# mh.net
KiCad netlist of a schematic drawn in EAGLE
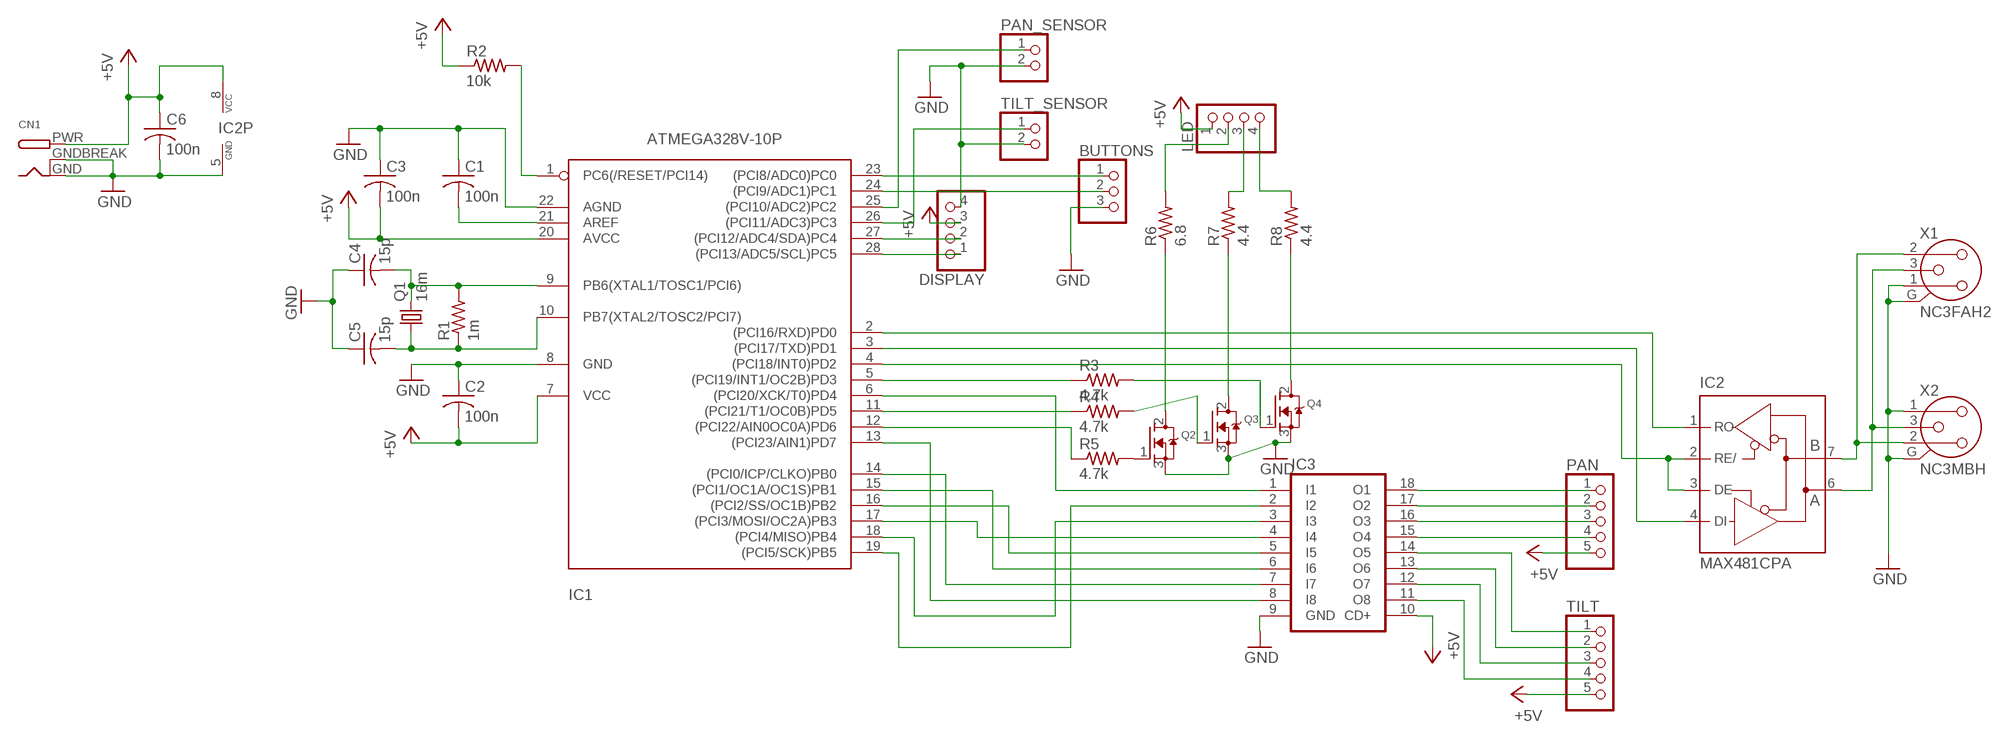
[diagram p0: schematic, sheet 1]

(export (version "E")
  (design (tool "Eeschema 10.0.6"))
  (components
    (comp (ref "BUTTONS")
      (value "PINHD-1X3")
      (footprint "eagle-import:1X03")
      (libsource (lib "eagle-import") (part "PINHD-1X3"))
    )
    (comp (ref "C1")
      (value "100n")
      (footprint "eagle-import:C025-024X044")
      (libsource (lib "eagle-import") (part "C-US025-024X044"))
    )
    (comp (ref "C2")
      (value "100n")
      (footprint "eagle-import:C025-024X044")
      (libsource (lib "eagle-import") (part "C-US025-024X044"))
    )
    (comp (ref "C3")
      (value "100n")
      (footprint "eagle-import:C025-024X044")
      (libsource (lib "eagle-import") (part "C-US025-024X044"))
    )
    (comp (ref "C4")
      (value "15p")
      (footprint "eagle-import:C050-024X044")
      (libsource (lib "eagle-import") (part "C-US050-024X044"))
    )
    (comp (ref "C5")
      (value "15p")
      (footprint "eagle-import:C050-024X044")
      (libsource (lib "eagle-import") (part "C-US050-024X044"))
    )
    (comp (ref "C6")
      (value "100n")
      (footprint "eagle-import:C025-024X044")
      (libsource (lib "eagle-import") (part "C-US025-024X044"))
    )
    (comp (ref "CN1")
      (value "DCBARRELPTH")
      (footprint "eagle-import:DCJACK_2MM_PTH")
      (libsource (lib "eagle-import") (part "DCBARRELPTH"))
    )
    (comp (ref "DISPLAY")
      (value "PINHD-1X4")
      (footprint "eagle-import:1X04")
      (libsource (lib "eagle-import") (part "PINHD-1X4"))
    )
    (comp (ref "IC1")
      (value "ATMEGA328V-10P")
      (footprint "eagle-import:DIL28-3")
      (libsource (lib "eagle-import") (part "ATMEGA328PV-10"))
    )
    (comp (ref "IC2")
      (value "MAX481CPA")
      (footprint "eagle-import:DIL08")
      (fields (field (name "MPN") "MAX481CPA+"))
      (libsource (lib "eagle-import") (part "MAX481CPA"))
    )
    (comp (ref "IC3")
      (value "ULN2803A")
      (footprint "eagle-import:DIL18")
      (libsource (lib "eagle-import") (part "ULN2803A"))
    )
    (comp (ref "LED")
      (value "PINHD-1X4")
      (footprint "eagle-import:1X04")
      (libsource (lib "eagle-import") (part "PINHD-1X4"))
    )
    (comp (ref "PAN")
      (value "PINHD-1X5")
      (footprint "eagle-import:1X05")
      (libsource (lib "eagle-import") (part "PINHD-1X5"))
    )
    (comp (ref "PAN_SENSOR")
      (value "PINHD-1X2")
      (footprint "eagle-import:1X02")
      (libsource (lib "eagle-import") (part "PINHD-1X2"))
    )
    (comp (ref "Q1")
      (value "16m")
      (footprint "eagle-import:HC49_S")
      (libsource (lib "eagle-import") (part "CRYSTALHC49S"))
    )
    (comp (ref "Q2")
      (value "MOSFET-NGDS_TO220V")
      (footprint "eagle-import:TO220V")
      (libsource (lib "eagle-import") (part "MOSFET-NGDS_TO220V"))
    )
    (comp (ref "Q3")
      (value "MOSFET-NGDS_TO220V")
      (footprint "eagle-import:TO220V")
      (libsource (lib "eagle-import") (part "MOSFET-NGDS_TO220V"))
    )
    (comp (ref "Q4")
      (value "MOSFET-NGDS_TO220V")
      (footprint "eagle-import:TO220V")
      (libsource (lib "eagle-import") (part "MOSFET-NGDS_TO220V"))
    )
    (comp (ref "R1")
      (value "1m")
      (footprint "eagle-import:0207_10")
      (libsource (lib "eagle-import") (part "R-US_0207/10"))
    )
    (comp (ref "R2")
      (value "10k")
      (footprint "eagle-import:0207_10")
      (libsource (lib "eagle-import") (part "R-US_0207/10"))
    )
    (comp (ref "R3")
      (value "4.7k")
      (footprint "eagle-import:0207_10")
      (libsource (lib "eagle-import") (part "R-US_0207/10"))
    )
    (comp (ref "R4")
      (value "4.7k")
      (footprint "eagle-import:0207_10")
      (libsource (lib "eagle-import") (part "R-US_0207/10"))
    )
    (comp (ref "R5")
      (value "4.7k")
      (footprint "eagle-import:0207_10")
      (libsource (lib "eagle-import") (part "R-US_0207/10"))
    )
    (comp (ref "R6")
      (value "6.8")
      (footprint "eagle-import:0617_17")
      (libsource (lib "eagle-import") (part "R-US_0617/17"))
    )
    (comp (ref "R7")
      (value "4.4")
      (footprint "eagle-import:0617_17")
      (libsource (lib "eagle-import") (part "R-US_0617/17"))
    )
    (comp (ref "R8")
      (value "4.4")
      (footprint "eagle-import:0617_17")
      (libsource (lib "eagle-import") (part "R-US_0617/17"))
    )
    (comp (ref "TILT")
      (value "PINHD-1X5")
      (footprint "eagle-import:1X05")
      (libsource (lib "eagle-import") (part "PINHD-1X5"))
    )
    (comp (ref "TILT_SENSOR")
      (value "PINHD-1X2")
      (footprint "eagle-import:1X02")
      (libsource (lib "eagle-import") (part "PINHD-1X2"))
    )
    (comp (ref "X1")
      (value "NC3FAH2")
      (footprint "eagle-import:NC3FAH2")
      (libsource (lib "eagle-import") (part "NC3FAH2"))
    )
    (comp (ref "X2")
      (value "NC3MBH")
      (footprint "eagle-import:NC3MBH")
      (fields (field (name "MF") "NEUTRIK"))
      (libsource (lib "eagle-import") (part "NC3MBH"))
    )
  )
  (nets
    (net (code "1") (name "+5V") (class "Default")
      (node (ref "C2") (pin "2") (pinfunction "2_2") (pintype "passive"))
      (node (ref "C3") (pin "2") (pinfunction "2_2") (pintype "passive"))
      (node (ref "C6") (pin "1") (pinfunction "1_1") (pintype "passive"))
      (node (ref "CN1") (pin "PWR") (pinfunction "PWR_PWR") (pintype "power_in"))
      (node (ref "DISPLAY") (pin "3") (pinfunction "3_3") (pintype "passive"))
      (node (ref "IC1") (pin "20") (pinfunction "AVCC_20") (pintype "bidirectional"))
      (node (ref "IC1") (pin "7") (pinfunction "VCC_7") (pintype "bidirectional"))
      (node (ref "IC2") (pin "8") (pinfunction "VCC_8") (pintype "power_in"))
      (node (ref "IC3") (pin "10") (pinfunction "CD+_10") (pintype "passive"))
      (node (ref "LED") (pin "1") (pinfunction "1_1") (pintype "passive"))
      (node (ref "PAN") (pin "5") (pinfunction "5_5") (pintype "passive"))
      (node (ref "R2") (pin "1") (pinfunction "1_1") (pintype "passive"))
      (node (ref "TILT") (pin "5") (pinfunction "5_5") (pintype "passive"))
    )
    (net (code "2") (name "GND") (class "Default")
      (node (ref "BUTTONS") (pin "3") (pinfunction "3_3") (pintype "passive"))
      (node (ref "C1") (pin "1") (pinfunction "1_1") (pintype "passive"))
      (node (ref "C2") (pin "1") (pinfunction "1_1") (pintype "passive"))
      (node (ref "C3") (pin "1") (pinfunction "1_1") (pintype "passive"))
      (node (ref "C4") (pin "1") (pinfunction "1_1") (pintype "passive"))
      (node (ref "C5") (pin "1") (pinfunction "1_1") (pintype "passive"))
      (node (ref "C6") (pin "2") (pinfunction "2_2") (pintype "passive"))
      (node (ref "CN1") (pin "GND") (pinfunction "GND_GND") (pintype "power_in"))
      (node (ref "CN1") (pin "GNDBREAK") (pinfunction "GNDBREAK_GNDBREAK") (pintype "power_in"))
      (node (ref "DISPLAY") (pin "4") (pinfunction "4_4") (pintype "passive"))
      (node (ref "IC1") (pin "22") (pinfunction "AGND_22") (pintype "bidirectional"))
      (node (ref "IC1") (pin "8") (pinfunction "GND_8") (pintype "bidirectional"))
      (node (ref "IC2") (pin "5") (pinfunction "GND_5") (pintype "power_in"))
      (node (ref "IC3") (pin "9") (pinfunction "GND_9") (pintype "power_in"))
      (node (ref "PAN_SENSOR") (pin "2") (pinfunction "2_2") (pintype "passive"))
      (node (ref "Q2") (pin "3") (pinfunction "S_3") (pintype "bidirectional"))
      (node (ref "Q3") (pin "3") (pinfunction "S_3") (pintype "bidirectional"))
      (node (ref "Q4") (pin "3") (pinfunction "S_3") (pintype "bidirectional"))
      (node (ref "TILT_SENSOR") (pin "2") (pinfunction "2_2") (pintype "passive"))
      (node (ref "X1") (pin "1") (pinfunction "2_1") (pintype "passive"))
      (node (ref "X1") (pin "G") (pinfunction "G_G") (pintype "passive"))
      (node (ref "X2") (pin "1") (pinfunction "1_1") (pintype "passive"))
      (node (ref "X2") (pin "G") (pinfunction "G_G") (pintype "passive"))
    )
    (net (code "3") (name "Net-(IC1-(PCI0{slash}ICP{slash}CLKO)PB0)") (class "Default")
      (node (ref "IC1") (pin "14") (pinfunction "(PCI0/ICP/CLKO)PB0_14") (pintype "bidirectional"))
      (node (ref "IC3") (pin "7") (pinfunction "I7_7") (pintype "input"))
    )
    (net (code "4") (name "Net-(IC1-(PCI1{slash}OC1A{slash}OC1S)PB1)") (class "Default")
      (node (ref "IC1") (pin "15") (pinfunction "(PCI1/OC1A/OC1S)PB1_15") (pintype "bidirectional"))
      (node (ref "IC3") (pin "6") (pinfunction "I6_6") (pintype "input"))
    )
    (net (code "5") (name "Net-(IC1-(PCI2{slash}SS{slash}OC1B)PB2)") (class "Default")
      (node (ref "IC1") (pin "16") (pinfunction "(PCI2/SS/OC1B)PB2_16") (pintype "bidirectional"))
      (node (ref "IC3") (pin "5") (pinfunction "I5_5") (pintype "input"))
    )
    (net (code "6") (name "Net-(IC1-(PCI3{slash}MOSI{slash}OC2A)PB3)") (class "Default")
      (node (ref "IC1") (pin "17") (pinfunction "(PCI3/MOSI/OC2A)PB3_17") (pintype "bidirectional"))
      (node (ref "IC3") (pin "4") (pinfunction "I4_4") (pintype "input"))
    )
    (net (code "7") (name "Net-(IC1-(PCI4{slash}MISO)PB4)") (class "Default")
      (node (ref "IC1") (pin "18") (pinfunction "(PCI4/MISO)PB4_18") (pintype "bidirectional"))
      (node (ref "IC3") (pin "3") (pinfunction "I3_3") (pintype "input"))
    )
    (net (code "8") (name "Net-(IC1-(PCI5{slash}SCK)PB5)") (class "Default")
      (node (ref "IC1") (pin "19") (pinfunction "(PCI5/SCK)PB5_19") (pintype "bidirectional"))
      (node (ref "IC3") (pin "2") (pinfunction "I2_2") (pintype "input"))
    )
    (net (code "9") (name "Net-(IC1-(PCI8{slash}ADC0)PC0)") (class "Default")
      (node (ref "BUTTONS") (pin "1") (pinfunction "1_1") (pintype "passive"))
      (node (ref "IC1") (pin "23") (pinfunction "(PCI8/ADC0)PC0_23") (pintype "bidirectional"))
    )
    (net (code "10") (name "Net-(IC1-(PCI9{slash}ADC1)PC1)") (class "Default")
      (node (ref "BUTTONS") (pin "2") (pinfunction "2_2") (pintype "passive"))
      (node (ref "IC1") (pin "24") (pinfunction "(PCI9/ADC1)PC1_24") (pintype "bidirectional"))
    )
    (net (code "11") (name "Net-(IC1-(PCI10{slash}ADC2)PC2)") (class "Default")
      (node (ref "IC1") (pin "25") (pinfunction "(PCI10/ADC2)PC2_25") (pintype "bidirectional"))
      (node (ref "PAN_SENSOR") (pin "1") (pinfunction "1_1") (pintype "passive"))
    )
    (net (code "12") (name "Net-(IC1-(PCI11{slash}ADC3)PC3)") (class "Default")
      (node (ref "IC1") (pin "26") (pinfunction "(PCI11/ADC3)PC3_26") (pintype "bidirectional"))
      (node (ref "TILT_SENSOR") (pin "1") (pinfunction "1_1") (pintype "passive"))
    )
    (net (code "13") (name "Net-(IC1-(PCI12{slash}ADC4{slash}SDA)PC4)") (class "Default")
      (node (ref "DISPLAY") (pin "2") (pinfunction "2_2") (pintype "passive"))
      (node (ref "IC1") (pin "27") (pinfunction "(PCI12/ADC4/SDA)PC4_27") (pintype "bidirectional"))
    )
    (net (code "14") (name "Net-(IC1-(PCI13{slash}ADC5{slash}SCL)PC5)") (class "Default")
      (node (ref "DISPLAY") (pin "1") (pinfunction "1_1") (pintype "passive"))
      (node (ref "IC1") (pin "28") (pinfunction "(PCI13/ADC5/SCL)PC5_28") (pintype "bidirectional"))
    )
    (net (code "15") (name "Net-(IC1-(PCI16{slash}RXD)PD0)") (class "Default")
      (node (ref "IC1") (pin "2") (pinfunction "(PCI16/RXD)PD0_2") (pintype "bidirectional"))
      (node (ref "IC2") (pin "1") (pinfunction "RO_1") (pintype "output"))
    )
    (net (code "16") (name "Net-(IC1-(PCI17{slash}TXD)PD1)") (class "Default")
      (node (ref "IC1") (pin "3") (pinfunction "(PCI17/TXD)PD1_3") (pintype "bidirectional"))
      (node (ref "IC2") (pin "4") (pinfunction "DI_4") (pintype "input"))
    )
    (net (code "17") (name "Net-(IC1-(PCI18{slash}INT0)PD2)") (class "Default")
      (node (ref "IC1") (pin "4") (pinfunction "(PCI18/INT0)PD2_4") (pintype "bidirectional"))
      (node (ref "IC2") (pin "2") (pinfunction "RE/_2") (pintype "input"))
      (node (ref "IC2") (pin "3") (pinfunction "DE_3") (pintype "input"))
    )
    (net (code "18") (name "Net-(IC1-(PCI19{slash}INT1{slash}OC2B)PD3)") (class "Default")
      (node (ref "IC1") (pin "5") (pinfunction "(PCI19/INT1/OC2B)PD3_5") (pintype "bidirectional"))
      (node (ref "R3") (pin "1") (pinfunction "1_1") (pintype "passive"))
    )
    (net (code "19") (name "Net-(IC1-(PCI20{slash}XCK{slash}T0)PD4)") (class "Default")
      (node (ref "IC1") (pin "6") (pinfunction "(PCI20/XCK/T0)PD4_6") (pintype "bidirectional"))
      (node (ref "IC3") (pin "1") (pinfunction "I1_1") (pintype "input"))
    )
    (net (code "20") (name "Net-(IC1-(PCI21{slash}T1{slash}OC0B)PD5)") (class "Default")
      (node (ref "IC1") (pin "11") (pinfunction "(PCI21/T1/OC0B)PD5_11") (pintype "bidirectional"))
      (node (ref "R4") (pin "1") (pinfunction "1_1") (pintype "passive"))
    )
    (net (code "21") (name "Net-(IC1-(PCI22{slash}AIN0OC0A)PD6)") (class "Default")
      (node (ref "IC1") (pin "12") (pinfunction "(PCI22/AIN0OC0A)PD6_12") (pintype "bidirectional"))
      (node (ref "R5") (pin "1") (pinfunction "1_1") (pintype "passive"))
    )
    (net (code "22") (name "Net-(IC1-(PCI23{slash}AIN1)PD7)") (class "Default")
      (node (ref "IC1") (pin "13") (pinfunction "(PCI23/AIN1)PD7_13") (pintype "bidirectional"))
      (node (ref "IC3") (pin "8") (pinfunction "I8_8") (pintype "input"))
    )
    (net (code "23") (name "Net-(IC1-AREF)") (class "Default")
      (node (ref "C1") (pin "2") (pinfunction "2_2") (pintype "passive"))
      (node (ref "IC1") (pin "21") (pinfunction "AREF_21") (pintype "bidirectional"))
    )
    (net (code "24") (name "Net-(IC1-PB6(XTAL1{slash}TOSC1{slash}PCI6))") (class "Default")
      (node (ref "C4") (pin "2") (pinfunction "2_2") (pintype "passive"))
      (node (ref "IC1") (pin "9") (pinfunction "PB6(XTAL1/TOSC1/PCI6)_9") (pintype "bidirectional"))
      (node (ref "Q1") (pin "2") (pinfunction "2_2") (pintype "passive"))
      (node (ref "R1") (pin "2") (pinfunction "2_2") (pintype "passive"))
    )
    (net (code "25") (name "Net-(IC1-PB7(XTAL2{slash}TOSC2{slash}PCI7))") (class "Default")
      (node (ref "C5") (pin "2") (pinfunction "2_2") (pintype "passive"))
      (node (ref "IC1") (pin "10") (pinfunction "PB7(XTAL2/TOSC2/PCI7)_10") (pintype "bidirectional"))
      (node (ref "Q1") (pin "1") (pinfunction "1_1") (pintype "passive"))
      (node (ref "R1") (pin "1") (pinfunction "1_1") (pintype "passive"))
    )
    (net (code "26") (name "Net-(IC1-PC6({slash}RESET{slash}PCI14))") (class "Default")
      (node (ref "IC1") (pin "1") (pinfunction "PC6(/RESET/PCI14)_1") (pintype "bidirectional"))
      (node (ref "R2") (pin "2") (pinfunction "2_2") (pintype "passive"))
    )
    (net (code "27") (name "Net-(IC2A-A)") (class "Default")
      (node (ref "IC2") (pin "6") (pinfunction "A_6") (pintype "passive"))
      (node (ref "X1") (pin "3") (pinfunction "3_3") (pintype "passive"))
      (node (ref "X2") (pin "3") (pinfunction "3_3") (pintype "passive"))
    )
    (net (code "28") (name "Net-(IC2A-B)") (class "Default")
      (node (ref "IC2") (pin "7") (pinfunction "B_7") (pintype "passive"))
      (node (ref "X1") (pin "2") (pinfunction "1_2") (pintype "passive"))
      (node (ref "X2") (pin "2") (pinfunction "2_2") (pintype "passive"))
    )
    (net (code "29") (name "Net-(IC3-O1)") (class "Default")
      (node (ref "IC3") (pin "18") (pinfunction "O1_18") (pintype "open_collector"))
      (node (ref "PAN") (pin "1") (pinfunction "1_1") (pintype "passive"))
    )
    (net (code "30") (name "Net-(IC3-O2)") (class "Default")
      (node (ref "IC3") (pin "17") (pinfunction "O2_17") (pintype "open_collector"))
      (node (ref "PAN") (pin "2") (pinfunction "2_2") (pintype "passive"))
    )
    (net (code "31") (name "Net-(IC3-O3)") (class "Default")
      (node (ref "IC3") (pin "16") (pinfunction "O3_16") (pintype "open_collector"))
      (node (ref "PAN") (pin "3") (pinfunction "3_3") (pintype "passive"))
    )
    (net (code "32") (name "Net-(IC3-O4)") (class "Default")
      (node (ref "IC3") (pin "15") (pinfunction "O4_15") (pintype "open_collector"))
      (node (ref "PAN") (pin "4") (pinfunction "4_4") (pintype "passive"))
    )
    (net (code "33") (name "Net-(IC3-O5)") (class "Default")
      (node (ref "IC3") (pin "14") (pinfunction "O5_14") (pintype "open_collector"))
      (node (ref "TILT") (pin "1") (pinfunction "1_1") (pintype "passive"))
    )
    (net (code "34") (name "Net-(IC3-O6)") (class "Default")
      (node (ref "IC3") (pin "13") (pinfunction "O6_13") (pintype "open_collector"))
      (node (ref "TILT") (pin "2") (pinfunction "2_2") (pintype "passive"))
    )
    (net (code "35") (name "Net-(IC3-O7)") (class "Default")
      (node (ref "IC3") (pin "12") (pinfunction "O7_12") (pintype "open_collector"))
      (node (ref "TILT") (pin "3") (pinfunction "3_3") (pintype "passive"))
    )
    (net (code "36") (name "Net-(IC3-O8)") (class "Default")
      (node (ref "IC3") (pin "11") (pinfunction "O8_11") (pintype "open_collector"))
      (node (ref "TILT") (pin "4") (pinfunction "4_4") (pintype "passive"))
    )
    (net (code "37") (name "Net-(LED-Pad2)") (class "Default")
      (node (ref "LED") (pin "2") (pinfunction "2_2") (pintype "passive"))
      (node (ref "R6") (pin "2") (pinfunction "2_2") (pintype "passive"))
    )
    (net (code "38") (name "Net-(LED-Pad3)") (class "Default")
      (node (ref "LED") (pin "3") (pinfunction "3_3") (pintype "passive"))
      (node (ref "R7") (pin "2") (pinfunction "2_2") (pintype "passive"))
    )
    (net (code "39") (name "Net-(LED-Pad4)") (class "Default")
      (node (ref "LED") (pin "4") (pinfunction "4_4") (pintype "passive"))
      (node (ref "R8") (pin "2") (pinfunction "2_2") (pintype "passive"))
    )
    (net (code "40") (name "Net-(Q2-D)") (class "Default")
      (node (ref "Q2") (pin "2") (pinfunction "D_2") (pintype "bidirectional"))
      (node (ref "R6") (pin "1") (pinfunction "1_1") (pintype "passive"))
    )
    (net (code "41") (name "Net-(Q2-G)") (class "Default")
      (node (ref "Q2") (pin "1") (pinfunction "G_1") (pintype "bidirectional"))
      (node (ref "R5") (pin "2") (pinfunction "2_2") (pintype "passive"))
    )
    (net (code "42") (name "Net-(Q3-D)") (class "Default")
      (node (ref "Q3") (pin "2") (pinfunction "D_2") (pintype "bidirectional"))
      (node (ref "R7") (pin "1") (pinfunction "1_1") (pintype "passive"))
    )
    (net (code "43") (name "Net-(Q3-G)") (class "Default")
      (node (ref "Q3") (pin "1") (pinfunction "G_1") (pintype "bidirectional"))
      (node (ref "R4") (pin "2") (pinfunction "2_2") (pintype "passive"))
    )
    (net (code "44") (name "Net-(Q4-D)") (class "Default")
      (node (ref "Q4") (pin "2") (pinfunction "D_2") (pintype "bidirectional"))
      (node (ref "R8") (pin "1") (pinfunction "1_1") (pintype "passive"))
    )
    (net (code "45") (name "Net-(Q4-G)") (class "Default")
      (node (ref "Q4") (pin "1") (pinfunction "G_1") (pintype "bidirectional"))
      (node (ref "R3") (pin "2") (pinfunction "2_2") (pintype "passive"))
    )
  )
)
